# basic.net
KiCad netlist of a schematic drawn in EAGLE
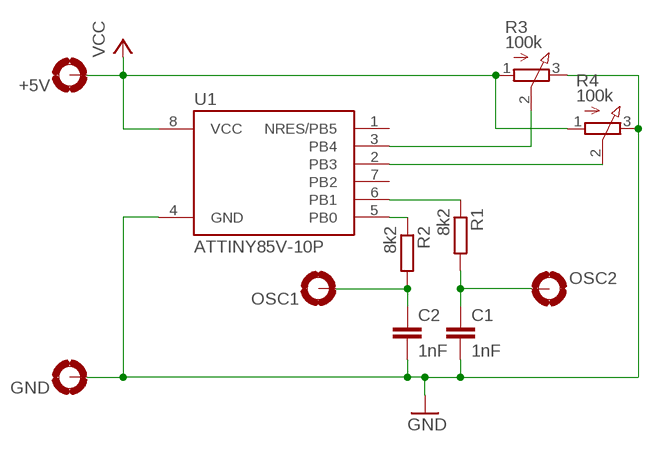
[diagram p0: schematic, sheet 1]

(export (version "E")
  (design (tool "Eeschema 10.0.6"))
  (components
    (comp (ref "+5V")
      (value "MOUNT-PAD-ROUND3.0")
      (footprint "eagle-import:3,0-PAD")
      (libsource (lib "eagle-import") (part "MOUNT-PAD-ROUND3.0"))
    )
    (comp (ref "C1")
      (value "1nF")
      (footprint "eagle-import:C2.5-4")
      (libsource (lib "eagle-import") (part "C2.5/4"))
    )
    (comp (ref "C2")
      (value "1nF")
      (footprint "eagle-import:C2.5-4")
      (libsource (lib "eagle-import") (part "C2.5/4"))
    )
    (comp (ref "GND")
      (value "MOUNT-PAD-ROUND3.0")
      (footprint "eagle-import:3,0-PAD")
      (libsource (lib "eagle-import") (part "MOUNT-PAD-ROUND3.0"))
    )
    (comp (ref "OSC1")
      (value "MOUNT-PAD-ROUND3.0")
      (footprint "eagle-import:3,0-PAD")
      (libsource (lib "eagle-import") (part "MOUNT-PAD-ROUND3.0"))
    )
    (comp (ref "OSC2")
      (value "MOUNT-PAD-ROUND3.0")
      (footprint "eagle-import:3,0-PAD")
      (libsource (lib "eagle-import") (part "MOUNT-PAD-ROUND3.0"))
    )
    (comp (ref "R1")
      (value "8k2")
      (footprint "eagle-import:0207_10")
      (libsource (lib "eagle-import") (part "R0207/10"))
    )
    (comp (ref "R2")
      (value "8k2")
      (footprint "eagle-import:0207_10")
      (libsource (lib "eagle-import") (part "R0207/10"))
    )
    (comp (ref "R3")
      (value "100k")
      (footprint "eagle-import:3RP_1610N")
      (libsource (lib "eagle-import") (part "3RP/1610N"))
    )
    (comp (ref "R4")
      (value "100k")
      (footprint "eagle-import:3RP_1610N")
      (libsource (lib "eagle-import") (part "3RP/1610N"))
    )
    (comp (ref "U1")
      (value "ATTINY85V-10P")
      (footprint "eagle-import:PDIP08_300MIL")
      (libsource (lib "eagle-import") (part "ATTINY85PV-10"))
    )
  )
  (nets
    (net (code "1") (name "GND") (class "Default")
      (node (ref "C1") (pin "2") (pinfunction "2_2") (pintype "passive"))
      (node (ref "C2") (pin "2") (pinfunction "2_2") (pintype "passive"))
      (node (ref "GND") (pin "B3,0") (pinfunction "MOUNT_B3,0") (pintype "passive"))
      (node (ref "R3") (pin "3") (pinfunction "E_3") (pintype "passive"))
      (node (ref "R4") (pin "3") (pinfunction "E_3") (pintype "passive"))
      (node (ref "U1") (pin "4") (pinfunction "GND_4") (pintype "power_in"))
    )
    (net (code "2") (name "Net-(OSC1-MOUNT)") (class "Default")
      (node (ref "C2") (pin "1") (pinfunction "1_1") (pintype "passive"))
      (node (ref "OSC1") (pin "B3,0") (pinfunction "MOUNT_B3,0") (pintype "passive"))
      (node (ref "R2") (pin "2") (pinfunction "2_2") (pintype "passive"))
    )
    (net (code "3") (name "Net-(OSC2-MOUNT)") (class "Default")
      (node (ref "C1") (pin "1") (pinfunction "1_1") (pintype "passive"))
      (node (ref "OSC2") (pin "B3,0") (pinfunction "MOUNT_B3,0") (pintype "passive"))
      (node (ref "R1") (pin "2") (pinfunction "2_2") (pintype "passive"))
    )
    (net (code "4") (name "Net-(R3-S)") (class "Default")
      (node (ref "R3") (pin "2") (pinfunction "S_2") (pintype "passive"))
      (node (ref "U1") (pin "3") (pinfunction "PB4_3") (pintype "bidirectional"))
    )
    (net (code "5") (name "Net-(R4-S)") (class "Default")
      (node (ref "R4") (pin "2") (pinfunction "S_2") (pintype "passive"))
      (node (ref "U1") (pin "2") (pinfunction "PB3_2") (pintype "bidirectional"))
    )
    (net (code "6") (name "Net-(U1-PB0)") (class "Default")
      (node (ref "R2") (pin "1") (pinfunction "1_1") (pintype "passive"))
      (node (ref "U1") (pin "5") (pinfunction "PB0_5") (pintype "bidirectional"))
    )
    (net (code "7") (name "Net-(U1-PB1)") (class "Default")
      (node (ref "R1") (pin "1") (pinfunction "1_1") (pintype "passive"))
      (node (ref "U1") (pin "6") (pinfunction "PB1_6") (pintype "bidirectional"))
    )
    (net (code "8") (name "VCC") (class "Default")
      (node (ref "+5V") (pin "B3,0") (pinfunction "MOUNT_B3,0") (pintype "passive"))
      (node (ref "R3") (pin "1") (pinfunction "A_1") (pintype "passive"))
      (node (ref "R4") (pin "1") (pinfunction "A_1") (pintype "passive"))
      (node (ref "U1") (pin "8") (pinfunction "VCC_8") (pintype "power_in"))
    )
    (net (code "9") (name "unconnected-(U1-NRES{slash}PB5-Pad1)") (class "Default")
      (node (ref "U1") (pin "1") (pinfunction "NRES/PB5_1") (pintype "bidirectional"))
    )
    (net (code "10") (name "unconnected-(U1-PB2-Pad7)") (class "Default")
      (node (ref "U1") (pin "7") (pinfunction "PB2_7") (pintype "bidirectional"))
    )
  )
)
